# TRV_ANAREN_V0_4.net
KiCad netlist of a schematic drawn in EAGLE
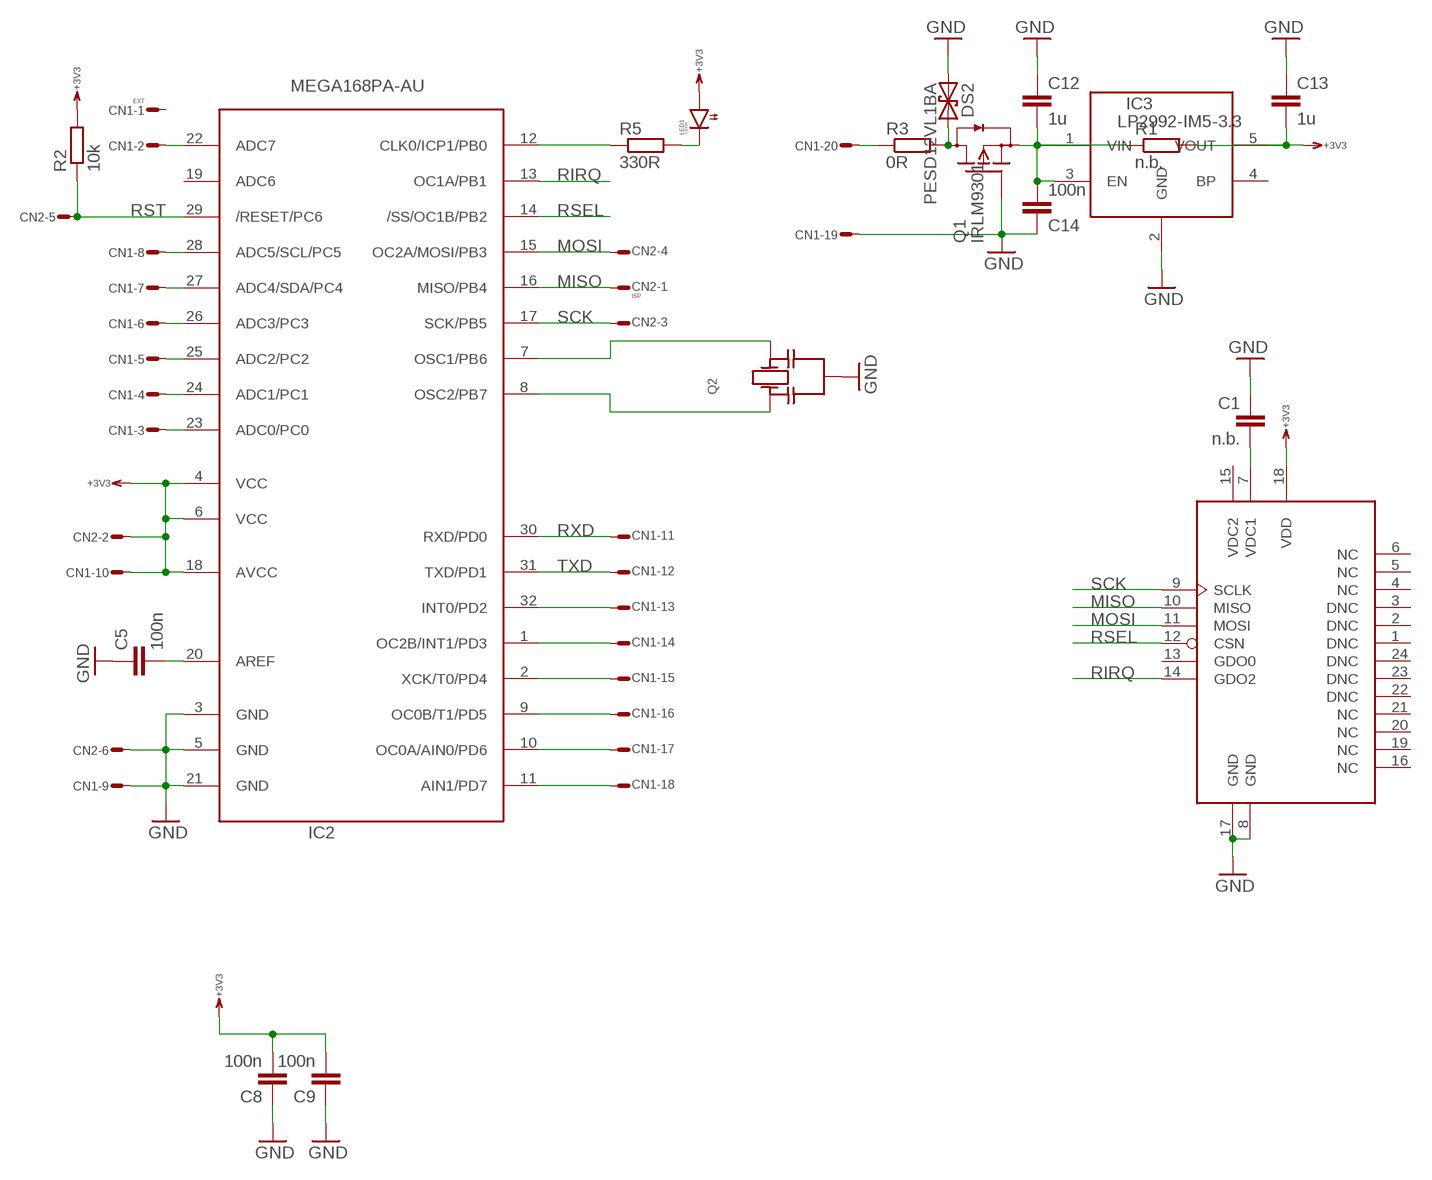
[diagram p0: schematic, sheet 1]

(export (version "E")
  (design (tool "Eeschema 10.0.6"))
  (components
    (comp (ref "C1")
      (value "n.b.")
      (footprint "eagle-import:0603")
      (libsource (lib "eagle-import") (part "C0603"))
    )
    (comp (ref "C5")
      (value "100n")
      (footprint "eagle-import:0603")
      (libsource (lib "eagle-import") (part "C0603"))
    )
    (comp (ref "C8")
      (value "100n")
      (footprint "eagle-import:0603")
      (libsource (lib "eagle-import") (part "C0603"))
    )
    (comp (ref "C9")
      (value "100n")
      (footprint "eagle-import:0603")
      (libsource (lib "eagle-import") (part "C0603"))
    )
    (comp (ref "C12")
      (value "1u")
      (footprint "eagle-import:0603")
      (libsource (lib "eagle-import") (part "C0603"))
    )
    (comp (ref "C13")
      (value "1u")
      (footprint "eagle-import:0603")
      (libsource (lib "eagle-import") (part "C0603"))
    )
    (comp (ref "C14")
      (value "100n")
      (footprint "eagle-import:0603")
      (libsource (lib "eagle-import") (part "C0603"))
    )
    (comp (ref "CN1")
      (value "EXT")
      (footprint "eagle-import:ML20")
      (libsource (lib "eagle-import") (part "ML20?E"))
    )
    (comp (ref "CN2")
      (value "ISP")
      (footprint "eagle-import:ML6")
      (libsource (lib "eagle-import") (part "ML6E"))
    )
    (comp (ref "DS2")
      (value "PESD12VL1BA")
      (footprint "eagle-import:SOD323")
      (libsource (lib "eagle-import") (part "TVS-U323"))
    )
    (comp (ref "IC2")
      (value "MEGA168PA-AU")
      (footprint "eagle-import:TQFP32-08")
      (libsource (lib "eagle-import") (part "MEGA168PA"))
    )
    (comp (ref "IC3")
      (value "LP2992-IM5-3.3")
      (footprint "eagle-import:SOT23-5")
      (libsource (lib "eagle-import") (part "LDO"))
    )
    (comp (ref "LED1")
      (value "LEDR")
      (footprint "eagle-import:0603")
      (libsource (lib "eagle-import") (part "LED0603"))
    )
    (comp (ref "Q1")
      (value "IRLM9301")
      (footprint "eagle-import:SOT23")
      (libsource (lib "eagle-import") (part "FET-PDSOT23"))
    )
    (comp (ref "Q2")
      (value "QRCR")
      (footprint "eagle-import:CR")
      (libsource (lib "eagle-import") (part "QRCR"))
    )
    (comp (ref "R1")
      (value "n.b.")
      (footprint "eagle-import:0603")
      (libsource (lib "eagle-import") (part "R0603"))
    )
    (comp (ref "R2")
      (value "10k")
      (footprint "eagle-import:0603")
      (libsource (lib "eagle-import") (part "R0603"))
    )
    (comp (ref "R3")
      (value "0R")
      (footprint "eagle-import:0603")
      (libsource (lib "eagle-import") (part "R0603"))
    )
    (comp (ref "R5")
      (value "330R")
      (footprint "eagle-import:0603")
      (libsource (lib "eagle-import") (part "R0603"))
    )
    (comp (ref "RF1")
      (value "ANARENC")
      (footprint "eagle-import:ANAREN_C")
      (libsource (lib "eagle-import") (part "ANARENC"))
    )
  )
  (nets
    (net (code "1") (name "+3V3") (class "Default")
      (node (ref "C13") (pin "2") (pinfunction "2_2") (pintype "passive"))
      (node (ref "C8") (pin "2") (pinfunction "2_2") (pintype "passive"))
      (node (ref "C9") (pin "2") (pinfunction "2_2") (pintype "passive"))
      (node (ref "CN1") (pin "10") (pinfunction "S_10") (pintype "passive"))
      (node (ref "CN2") (pin "2") (pinfunction "S_2") (pintype "passive"))
      (node (ref "IC2") (pin "18") (pinfunction "AVCC_18") (pintype "bidirectional"))
      (node (ref "IC2") (pin "4") (pinfunction "VCC_4") (pintype "bidirectional"))
      (node (ref "IC2") (pin "6") (pinfunction "VCC_6") (pintype "bidirectional"))
      (node (ref "IC3") (pin "5") (pinfunction "VOUT_5") (pintype "bidirectional"))
      (node (ref "LED1") (pin "1") (pinfunction "A_1") (pintype "bidirectional"))
      (node (ref "R1") (pin "2") (pinfunction "2_2") (pintype "passive"))
      (node (ref "R2") (pin "2") (pinfunction "2_2") (pintype "passive"))
      (node (ref "RF1") (pin "18") (pinfunction "VDD_18") (pintype "bidirectional"))
    )
    (net (code "2") (name "/MISO") (class "Default")
      (node (ref "CN2") (pin "1") (pinfunction "S_1") (pintype "passive"))
      (node (ref "IC2") (pin "16") (pinfunction "MISO/PB4_16") (pintype "bidirectional"))
      (node (ref "RF1") (pin "10") (pinfunction "MISO_10") (pintype "output"))
    )
    (net (code "3") (name "/MOSI") (class "Default")
      (node (ref "CN2") (pin "4") (pinfunction "S_4") (pintype "passive"))
      (node (ref "IC2") (pin "15") (pinfunction "OC2A/MOSI/PB3_15") (pintype "bidirectional"))
      (node (ref "RF1") (pin "11") (pinfunction "MOSI_11") (pintype "input"))
    )
    (net (code "4") (name "/RIRQ") (class "Default")
      (node (ref "IC2") (pin "13") (pinfunction "OC1A/PB1_13") (pintype "bidirectional"))
      (node (ref "RF1") (pin "14") (pinfunction "GDO2_14") (pintype "bidirectional"))
    )
    (net (code "5") (name "/RSEL") (class "Default")
      (node (ref "IC2") (pin "14") (pinfunction "/SS/OC1B/PB2_14") (pintype "bidirectional"))
      (node (ref "RF1") (pin "12") (pinfunction "CSN_12") (pintype "input"))
    )
    (net (code "6") (name "/RST") (class "Default")
      (node (ref "CN2") (pin "5") (pinfunction "S_5") (pintype "passive"))
      (node (ref "IC2") (pin "29") (pinfunction "/RESET/PC6_29") (pintype "bidirectional"))
      (node (ref "R2") (pin "1") (pinfunction "1_1") (pintype "passive"))
    )
    (net (code "7") (name "/RXD") (class "Default")
      (node (ref "CN1") (pin "11") (pinfunction "S_11") (pintype "passive"))
      (node (ref "IC2") (pin "30") (pinfunction "RXD/PD0_30") (pintype "bidirectional"))
    )
    (net (code "8") (name "/SCK") (class "Default")
      (node (ref "CN2") (pin "3") (pinfunction "S_3") (pintype "passive"))
      (node (ref "IC2") (pin "17") (pinfunction "SCK/PB5_17") (pintype "bidirectional"))
      (node (ref "RF1") (pin "9") (pinfunction "SCLK_9") (pintype "input"))
    )
    (net (code "9") (name "/TXD") (class "Default")
      (node (ref "CN1") (pin "12") (pinfunction "S_12") (pintype "passive"))
      (node (ref "IC2") (pin "31") (pinfunction "TXD/PD1_31") (pintype "bidirectional"))
    )
    (net (code "10") (name "GND") (class "Default")
      (node (ref "C1") (pin "1") (pinfunction "1_1") (pintype "passive"))
      (node (ref "C12") (pin "1") (pinfunction "1_1") (pintype "passive"))
      (node (ref "C13") (pin "1") (pinfunction "1_1") (pintype "passive"))
      (node (ref "C14") (pin "1") (pinfunction "1_1") (pintype "passive"))
      (node (ref "C5") (pin "1") (pinfunction "1_1") (pintype "passive"))
      (node (ref "C8") (pin "1") (pinfunction "1_1") (pintype "passive"))
      (node (ref "C9") (pin "1") (pinfunction "1_1") (pintype "passive"))
      (node (ref "CN1") (pin "19") (pinfunction "S_19") (pintype "passive"))
      (node (ref "CN1") (pin "9") (pinfunction "S_9") (pintype "passive"))
      (node (ref "CN2") (pin "6") (pinfunction "S_6") (pintype "passive"))
      (node (ref "DS2") (pin "A") (pinfunction "1_A") (pintype "passive"))
      (node (ref "IC2") (pin "21") (pinfunction "GND_21") (pintype "bidirectional"))
      (node (ref "IC2") (pin "3") (pinfunction "GND_3") (pintype "bidirectional"))
      (node (ref "IC2") (pin "5") (pinfunction "GND_5") (pintype "bidirectional"))
      (node (ref "IC3") (pin "2") (pinfunction "GND_2") (pintype "bidirectional"))
      (node (ref "Q1") (pin "1") (pinfunction "G_1") (pintype "passive"))
      (node (ref "Q2") (pin "M") (pinfunction "M_M") (pintype "passive"))
      (node (ref "RF1") (pin "17") (pinfunction "GND_17") (pintype "bidirectional"))
      (node (ref "RF1") (pin "8") (pinfunction "GND_8") (pintype "bidirectional"))
    )
    (net (code "11") (name "Net-(CN1E-S)") (class "Default")
      (node (ref "CN1") (pin "13") (pinfunction "S_13") (pintype "passive"))
      (node (ref "IC2") (pin "32") (pinfunction "INT0/PD2_32") (pintype "bidirectional"))
    )
    (net (code "12") (name "Net-(CN1F-S)") (class "Default")
      (node (ref "CN1") (pin "14") (pinfunction "S_14") (pintype "passive"))
      (node (ref "IC2") (pin "1") (pinfunction "OC2B/INT1/PD3_1") (pintype "bidirectional"))
    )
    (net (code "13") (name "Net-(CN1G-S)") (class "Default")
      (node (ref "CN1") (pin "15") (pinfunction "S_15") (pintype "passive"))
      (node (ref "IC2") (pin "2") (pinfunction "XCK/T0/PD4_2") (pintype "bidirectional"))
    )
    (net (code "14") (name "Net-(CN1H-S)") (class "Default")
      (node (ref "CN1") (pin "16") (pinfunction "S_16") (pintype "passive"))
      (node (ref "IC2") (pin "9") (pinfunction "OC0B/T1/PD5_9") (pintype "bidirectional"))
    )
    (net (code "15") (name "Net-(CN1I-S)") (class "Default")
      (node (ref "CN1") (pin "17") (pinfunction "S_17") (pintype "passive"))
      (node (ref "IC2") (pin "10") (pinfunction "OC0A/AIN0/PD6_10") (pintype "bidirectional"))
    )
    (net (code "16") (name "Net-(CN1J-S)") (class "Default")
      (node (ref "CN1") (pin "18") (pinfunction "S_18") (pintype "passive"))
      (node (ref "IC2") (pin "11") (pinfunction "AIN1/PD7_11") (pintype "bidirectional"))
    )
    (net (code "17") (name "Net-(CN1L-S)") (class "Default")
      (node (ref "CN1") (pin "2") (pinfunction "S_2") (pintype "passive"))
      (node (ref "IC2") (pin "22") (pinfunction "ADC7_22") (pintype "bidirectional"))
    )
    (net (code "18") (name "Net-(CN1M-S)") (class "Default")
      (node (ref "CN1") (pin "20") (pinfunction "S_20") (pintype "passive"))
      (node (ref "R3") (pin "1") (pinfunction "1_1") (pintype "passive"))
    )
    (net (code "19") (name "Net-(CN1N-S)") (class "Default")
      (node (ref "CN1") (pin "3") (pinfunction "S_3") (pintype "passive"))
      (node (ref "IC2") (pin "23") (pinfunction "ADC0/PC0_23") (pintype "bidirectional"))
    )
    (net (code "20") (name "Net-(CN1O-S)") (class "Default")
      (node (ref "CN1") (pin "4") (pinfunction "S_4") (pintype "passive"))
      (node (ref "IC2") (pin "24") (pinfunction "ADC1/PC1_24") (pintype "bidirectional"))
    )
    (net (code "21") (name "Net-(CN1P-S)") (class "Default")
      (node (ref "CN1") (pin "5") (pinfunction "S_5") (pintype "passive"))
      (node (ref "IC2") (pin "25") (pinfunction "ADC2/PC2_25") (pintype "bidirectional"))
    )
    (net (code "22") (name "Net-(CN1Q-S)") (class "Default")
      (node (ref "CN1") (pin "6") (pinfunction "S_6") (pintype "passive"))
      (node (ref "IC2") (pin "26") (pinfunction "ADC3/PC3_26") (pintype "bidirectional"))
    )
    (net (code "23") (name "Net-(CN1R-S)") (class "Default")
      (node (ref "CN1") (pin "7") (pinfunction "S_7") (pintype "passive"))
      (node (ref "IC2") (pin "27") (pinfunction "ADC4/SDA/PC4_27") (pintype "bidirectional"))
    )
    (net (code "24") (name "Net-(CN1S-S)") (class "Default")
      (node (ref "CN1") (pin "8") (pinfunction "S_8") (pintype "passive"))
      (node (ref "IC2") (pin "28") (pinfunction "ADC5/SCL/PC5_28") (pintype "bidirectional"))
    )
    (net (code "25") (name "Net-(DS2-2)") (class "Default")
      (node (ref "DS2") (pin "C") (pinfunction "2_C") (pintype "passive"))
      (node (ref "Q1") (pin "3") (pinfunction "D_3") (pintype "passive"))
      (node (ref "R3") (pin "2") (pinfunction "2_2") (pintype "passive"))
    )
    (net (code "26") (name "Net-(IC2-AREF)") (class "Default")
      (node (ref "C5") (pin "2") (pinfunction "2_2") (pintype "passive"))
      (node (ref "IC2") (pin "20") (pinfunction "AREF_20") (pintype "bidirectional"))
    )
    (net (code "27") (name "Net-(IC2-CLK0{slash}ICP1{slash}PB0)") (class "Default")
      (node (ref "IC2") (pin "12") (pinfunction "CLK0/ICP1/PB0_12") (pintype "bidirectional"))
      (node (ref "R5") (pin "1") (pinfunction "1_1") (pintype "passive"))
    )
    (net (code "28") (name "Net-(IC2-OSC1{slash}PB6)") (class "Default")
      (node (ref "IC2") (pin "7") (pinfunction "OSC1/PB6_7") (pintype "bidirectional"))
      (node (ref "Q2") (pin "2") (pinfunction "2_2") (pintype "passive"))
    )
    (net (code "29") (name "Net-(IC2-OSC2{slash}PB7)") (class "Default")
      (node (ref "IC2") (pin "8") (pinfunction "OSC2/PB7_8") (pintype "bidirectional"))
      (node (ref "Q2") (pin "1") (pinfunction "1_1") (pintype "passive"))
    )
    (net (code "30") (name "Net-(IC3-EN)") (class "Default")
      (node (ref "C12") (pin "2") (pinfunction "2_2") (pintype "passive"))
      (node (ref "C14") (pin "2") (pinfunction "2_2") (pintype "passive"))
      (node (ref "IC3") (pin "1") (pinfunction "VIN_1") (pintype "bidirectional"))
      (node (ref "IC3") (pin "3") (pinfunction "EN_3") (pintype "bidirectional"))
      (node (ref "Q1") (pin "2") (pinfunction "S_2") (pintype "passive"))
      (node (ref "R1") (pin "1") (pinfunction "1_1") (pintype "passive"))
    )
    (net (code "31") (name "Net-(LED1-C)") (class "Default")
      (node (ref "LED1") (pin "2") (pinfunction "C_2") (pintype "bidirectional"))
      (node (ref "R5") (pin "2") (pinfunction "2_2") (pintype "passive"))
    )
    (net (code "32") (name "Net-(RF1-VDC1)") (class "Default")
      (node (ref "C1") (pin "2") (pinfunction "2_2") (pintype "passive"))
      (node (ref "RF1") (pin "7") (pinfunction "VDC1_7") (pintype "bidirectional"))
    )
    (net (code "33") (name "unconnected-(CN1A-S-Pad1)") (class "Default")
      (node (ref "CN1") (pin "1") (pinfunction "S_1") (pintype "passive"))
    )
    (net (code "34") (name "unconnected-(IC2-ADC6-Pad19)") (class "Default")
      (node (ref "IC2") (pin "19") (pinfunction "ADC6_19") (pintype "bidirectional"))
    )
    (net (code "35") (name "unconnected-(IC3-BP-Pad4)") (class "Default")
      (node (ref "IC3") (pin "4") (pinfunction "BP_4") (pintype "bidirectional"))
    )
    (net (code "36") (name "unconnected-(RF1-DNC-Pad1)") (class "Default")
      (node (ref "RF1") (pin "1") (pinfunction "DNC_1") (pintype "bidirectional"))
    )
    (net (code "37") (name "unconnected-(RF1-DNC-Pad2)") (class "Default")
      (node (ref "RF1") (pin "2") (pinfunction "DNC_2") (pintype "bidirectional"))
    )
    (net (code "38") (name "unconnected-(RF1-DNC-Pad3)") (class "Default")
      (node (ref "RF1") (pin "3") (pinfunction "DNC_3") (pintype "bidirectional"))
    )
    (net (code "39") (name "unconnected-(RF1-DNC-Pad22)") (class "Default")
      (node (ref "RF1") (pin "22") (pinfunction "DNC_22") (pintype "bidirectional"))
    )
    (net (code "40") (name "unconnected-(RF1-DNC-Pad23)") (class "Default")
      (node (ref "RF1") (pin "23") (pinfunction "DNC_23") (pintype "bidirectional"))
    )
    (net (code "41") (name "unconnected-(RF1-DNC-Pad24)") (class "Default")
      (node (ref "RF1") (pin "24") (pinfunction "DNC_24") (pintype "bidirectional"))
    )
    (net (code "42") (name "unconnected-(RF1-GDO0-Pad13)") (class "Default")
      (node (ref "RF1") (pin "13") (pinfunction "GDO0_13") (pintype "bidirectional"))
    )
    (net (code "43") (name "unconnected-(RF1-NC-Pad4)") (class "Default")
      (node (ref "RF1") (pin "4") (pinfunction "NC_4") (pintype "bidirectional"))
    )
    (net (code "44") (name "unconnected-(RF1-NC-Pad5)") (class "Default")
      (node (ref "RF1") (pin "5") (pinfunction "NC_5") (pintype "bidirectional"))
    )
    (net (code "45") (name "unconnected-(RF1-NC-Pad6)") (class "Default")
      (node (ref "RF1") (pin "6") (pinfunction "NC_6") (pintype "bidirectional"))
    )
    (net (code "46") (name "unconnected-(RF1-NC-Pad16)") (class "Default")
      (node (ref "RF1") (pin "16") (pinfunction "NC_16") (pintype "bidirectional"))
    )
    (net (code "47") (name "unconnected-(RF1-NC-Pad19)") (class "Default")
      (node (ref "RF1") (pin "19") (pinfunction "NC_19") (pintype "bidirectional"))
    )
    (net (code "48") (name "unconnected-(RF1-NC-Pad20)") (class "Default")
      (node (ref "RF1") (pin "20") (pinfunction "NC_20") (pintype "bidirectional"))
    )
    (net (code "49") (name "unconnected-(RF1-NC-Pad21)") (class "Default")
      (node (ref "RF1") (pin "21") (pinfunction "NC_21") (pintype "bidirectional"))
    )
    (net (code "50") (name "unconnected-(RF1-VDC2-Pad15)") (class "Default")
      (node (ref "RF1") (pin "15") (pinfunction "VDC2_15") (pintype "bidirectional"))
    )
  )
)
